# CONNECTEUR_4.net
KiCad netlist of a schematic drawn in Altium Designer
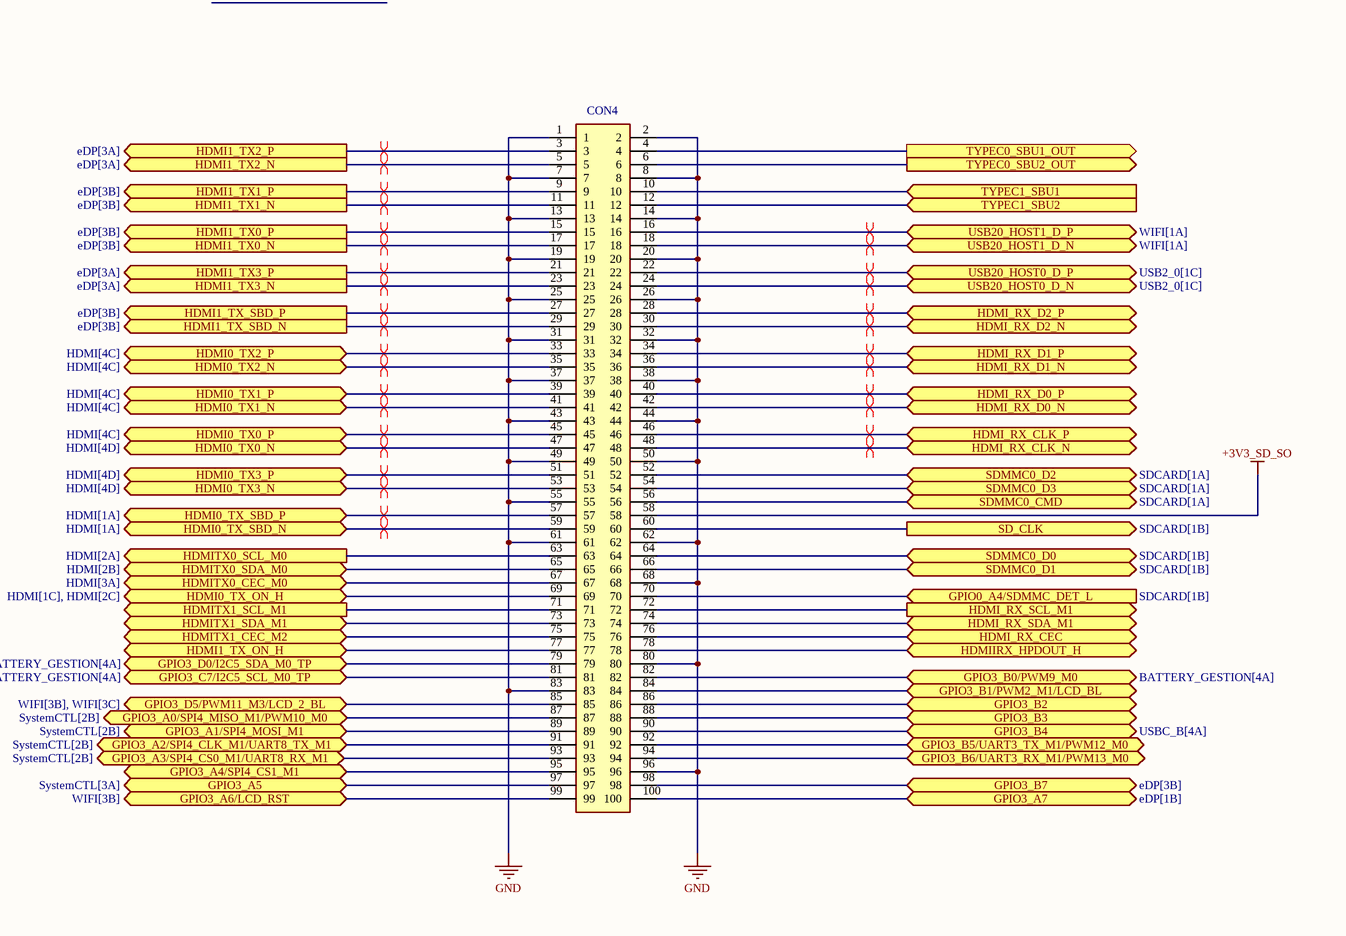
[diagram p0: CONNECTEUR_4.SchDoc, right]

(export (version "E")
  (design (tool "Eeschema 10.0.6"))
  (components
    (comp (ref "CON4")
      (value "DF40HC")
      (footprint "SamacSys:DF40HC30100DS04V51")
      (description "Stacking Board Connector, DF40 Series, Receptacle, 0.4 mm, 100, Surface Mount, G")
      (fields
        (field (name "MANUFACTURER_PART_NUMBER") "DF40HC(3.0)-100DS-0.4V(51")
        (field (name "MOUSER PART NUMBER") "798-DF40HC30100DS451")
      )
      (libsource (lib "SamacSys") (part "DF40HC(3.0)-100DS-0.4V(51)"))
    )
  )
  (nets
    (net (code "1") (name "+3V3_SD_SO") (class "Default")
      (node (ref "CON4") (pin "58") (pinfunction "58_58") (pintype "passive"))
    )
    (net (code "2") (name "/GPIO0_A4{slash}SDMMC_DET_L") (class "Default")
      (node (ref "CON4") (pin "70") (pinfunction "70_70") (pintype "passive"))
    )
    (net (code "3") (name "/GPIO3_A0{slash}SPI4_MISO_M1{slash}PWM10_M0") (class "Default")
      (node (ref "CON4") (pin "87") (pinfunction "87_87") (pintype "passive"))
    )
    (net (code "4") (name "/GPIO3_A1{slash}SPI4_MOSI_M1") (class "Default")
      (node (ref "CON4") (pin "89") (pinfunction "89_89") (pintype "passive"))
    )
    (net (code "5") (name "/GPIO3_A2{slash}SPI4_CLK_M1{slash}UART8_TX_M1") (class "Default")
      (node (ref "CON4") (pin "91") (pinfunction "91_91") (pintype "passive"))
    )
    (net (code "6") (name "/GPIO3_A3{slash}SPI4_CS0_M1{slash}UART8_RX_M1") (class "Default")
      (node (ref "CON4") (pin "93") (pinfunction "93_93") (pintype "passive"))
    )
    (net (code "7") (name "/GPIO3_A4{slash}SPI4_CS1_M1") (class "Default")
      (node (ref "CON4") (pin "95") (pinfunction "95_95") (pintype "passive"))
    )
    (net (code "8") (name "/GPIO3_A5") (class "Default")
      (node (ref "CON4") (pin "97") (pinfunction "97_97") (pintype "passive"))
    )
    (net (code "9") (name "/GPIO3_A6{slash}LCD_RST") (class "Default")
      (node (ref "CON4") (pin "99") (pinfunction "99_99") (pintype "passive"))
    )
    (net (code "10") (name "/GPIO3_A7") (class "Default")
      (node (ref "CON4") (pin "100") (pinfunction "100_100") (pintype "passive"))
    )
    (net (code "11") (name "/GPIO3_B0{slash}PWM9_M0") (class "Default")
      (node (ref "CON4") (pin "82") (pinfunction "82_82") (pintype "passive"))
    )
    (net (code "12") (name "/GPIO3_B1{slash}PWM2_M1{slash}LCD_BL") (class "Default")
      (node (ref "CON4") (pin "84") (pinfunction "84_84") (pintype "passive"))
    )
    (net (code "13") (name "/GPIO3_B2") (class "Default")
      (node (ref "CON4") (pin "86") (pinfunction "86_86") (pintype "passive"))
    )
    (net (code "14") (name "/GPIO3_B3") (class "Default")
      (node (ref "CON4") (pin "88") (pinfunction "88_88") (pintype "passive"))
    )
    (net (code "15") (name "/GPIO3_B4") (class "Default")
      (node (ref "CON4") (pin "90") (pinfunction "90_90") (pintype "passive"))
    )
    (net (code "16") (name "/GPIO3_B5{slash}UART3_TX_M1{slash}PWM12_M0") (class "Default")
      (node (ref "CON4") (pin "92") (pinfunction "92_92") (pintype "passive"))
    )
    (net (code "17") (name "/GPIO3_B6{slash}UART3_RX_M1{slash}PWM13_M0") (class "Default")
      (node (ref "CON4") (pin "94") (pinfunction "94_94") (pintype "passive"))
    )
    (net (code "18") (name "/GPIO3_B7") (class "Default")
      (node (ref "CON4") (pin "98") (pinfunction "98_98") (pintype "passive"))
    )
    (net (code "19") (name "/GPIO3_C7{slash}I2C5_SCL_M0_TP") (class "Default")
      (node (ref "CON4") (pin "81") (pinfunction "81_81") (pintype "passive"))
    )
    (net (code "20") (name "/GPIO3_D0{slash}I2C5_SDA_M0_TP") (class "Default")
      (node (ref "CON4") (pin "79") (pinfunction "79_79") (pintype "passive"))
    )
    (net (code "21") (name "/GPIO3_D5{slash}PWM11_M3{slash}LCD_2_BL") (class "Default")
      (node (ref "CON4") (pin "85") (pinfunction "85_85") (pintype "passive"))
    )
    (net (code "22") (name "/HDMI0_TX0_N") (class "Default")
      (node (ref "CON4") (pin "47") (pinfunction "47_47") (pintype "passive"))
    )
    (net (code "23") (name "/HDMI0_TX0_P") (class "Default")
      (node (ref "CON4") (pin "45") (pinfunction "45_45") (pintype "passive"))
    )
    (net (code "24") (name "/HDMI0_TX1_N") (class "Default")
      (node (ref "CON4") (pin "41") (pinfunction "41_41") (pintype "passive"))
    )
    (net (code "25") (name "/HDMI0_TX1_P") (class "Default")
      (node (ref "CON4") (pin "39") (pinfunction "39_39") (pintype "passive"))
    )
    (net (code "26") (name "/HDMI0_TX2_N") (class "Default")
      (node (ref "CON4") (pin "35") (pinfunction "35_35") (pintype "passive"))
    )
    (net (code "27") (name "/HDMI0_TX2_P") (class "Default")
      (node (ref "CON4") (pin "33") (pinfunction "33_33") (pintype "passive"))
    )
    (net (code "28") (name "/HDMI0_TX3_N") (class "Default")
      (node (ref "CON4") (pin "53") (pinfunction "53_53") (pintype "passive"))
    )
    (net (code "29") (name "/HDMI0_TX3_P") (class "Default")
      (node (ref "CON4") (pin "51") (pinfunction "51_51") (pintype "passive"))
    )
    (net (code "30") (name "/HDMI0_TX_ON_H") (class "Default")
      (node (ref "CON4") (pin "69") (pinfunction "69_69") (pintype "passive"))
    )
    (net (code "31") (name "/HDMI0_TX_SBD_N") (class "Default")
      (node (ref "CON4") (pin "59") (pinfunction "59_59") (pintype "passive"))
    )
    (net (code "32") (name "/HDMI0_TX_SBD_P") (class "Default")
      (node (ref "CON4") (pin "57") (pinfunction "57_57") (pintype "passive"))
    )
    (net (code "33") (name "/HDMI1_TX0_N") (class "Default")
      (node (ref "CON4") (pin "17") (pinfunction "17_17") (pintype "passive"))
    )
    (net (code "34") (name "/HDMI1_TX0_P") (class "Default")
      (node (ref "CON4") (pin "15") (pinfunction "15_15") (pintype "passive"))
    )
    (net (code "35") (name "/HDMI1_TX1_N") (class "Default")
      (node (ref "CON4") (pin "11") (pinfunction "11_11") (pintype "passive"))
    )
    (net (code "36") (name "/HDMI1_TX1_P") (class "Default")
      (node (ref "CON4") (pin "9") (pinfunction "9_9") (pintype "passive"))
    )
    (net (code "37") (name "/HDMI1_TX2_N") (class "Default")
      (node (ref "CON4") (pin "5") (pinfunction "5_5") (pintype "passive"))
    )
    (net (code "38") (name "/HDMI1_TX2_P") (class "Default")
      (node (ref "CON4") (pin "3") (pinfunction "3_3") (pintype "passive"))
    )
    (net (code "39") (name "/HDMI1_TX3_N") (class "Default")
      (node (ref "CON4") (pin "23") (pinfunction "23_23") (pintype "passive"))
    )
    (net (code "40") (name "/HDMI1_TX3_P") (class "Default")
      (node (ref "CON4") (pin "21") (pinfunction "21_21") (pintype "passive"))
    )
    (net (code "41") (name "/HDMI1_TX_ON_H") (class "Default")
      (node (ref "CON4") (pin "77") (pinfunction "77_77") (pintype "passive"))
    )
    (net (code "42") (name "/HDMI1_TX_SBD_N") (class "Default")
      (node (ref "CON4") (pin "29") (pinfunction "29_29") (pintype "passive"))
    )
    (net (code "43") (name "/HDMI1_TX_SBD_P") (class "Default")
      (node (ref "CON4") (pin "27") (pinfunction "27_27") (pintype "passive"))
    )
    (net (code "44") (name "/HDMIIRX_HPDOUT_H") (class "Default")
      (node (ref "CON4") (pin "78") (pinfunction "78_78") (pintype "passive"))
    )
    (net (code "45") (name "/HDMITX0_CEC_M0") (class "Default")
      (node (ref "CON4") (pin "67") (pinfunction "67_67") (pintype "passive"))
    )
    (net (code "46") (name "/HDMITX0_SCL_M0") (class "Default")
      (node (ref "CON4") (pin "63") (pinfunction "63_63") (pintype "passive"))
    )
    (net (code "47") (name "/HDMITX0_SDA_M0") (class "Default")
      (node (ref "CON4") (pin "65") (pinfunction "65_65") (pintype "passive"))
    )
    (net (code "48") (name "/HDMITX1_CEC_M2") (class "Default")
      (node (ref "CON4") (pin "75") (pinfunction "75_75") (pintype "passive"))
    )
    (net (code "49") (name "/HDMITX1_SCL_M1") (class "Default")
      (node (ref "CON4") (pin "71") (pinfunction "71_71") (pintype "passive"))
    )
    (net (code "50") (name "/HDMITX1_SDA_M1") (class "Default")
      (node (ref "CON4") (pin "73") (pinfunction "73_73") (pintype "passive"))
    )
    (net (code "51") (name "/HDMI_RX_CEC") (class "Default")
      (node (ref "CON4") (pin "76") (pinfunction "76_76") (pintype "passive"))
    )
    (net (code "52") (name "/HDMI_RX_CLK_N") (class "Default")
      (node (ref "CON4") (pin "48") (pinfunction "48_48") (pintype "passive"))
    )
    (net (code "53") (name "/HDMI_RX_CLK_P") (class "Default")
      (node (ref "CON4") (pin "46") (pinfunction "46_46") (pintype "passive"))
    )
    (net (code "54") (name "/HDMI_RX_D0_N") (class "Default")
      (node (ref "CON4") (pin "42") (pinfunction "42_42") (pintype "passive"))
    )
    (net (code "55") (name "/HDMI_RX_D0_P") (class "Default")
      (node (ref "CON4") (pin "40") (pinfunction "40_40") (pintype "passive"))
    )
    (net (code "56") (name "/HDMI_RX_D1_N") (class "Default")
      (node (ref "CON4") (pin "36") (pinfunction "36_36") (pintype "passive"))
    )
    (net (code "57") (name "/HDMI_RX_D1_P") (class "Default")
      (node (ref "CON4") (pin "34") (pinfunction "34_34") (pintype "passive"))
    )
    (net (code "58") (name "/HDMI_RX_D2_N") (class "Default")
      (node (ref "CON4") (pin "30") (pinfunction "30_30") (pintype "passive"))
    )
    (net (code "59") (name "/HDMI_RX_D2_P") (class "Default")
      (node (ref "CON4") (pin "28") (pinfunction "28_28") (pintype "passive"))
    )
    (net (code "60") (name "/HDMI_RX_SCL_M1") (class "Default")
      (node (ref "CON4") (pin "72") (pinfunction "72_72") (pintype "passive"))
    )
    (net (code "61") (name "/HDMI_RX_SDA_M1") (class "Default")
      (node (ref "CON4") (pin "74") (pinfunction "74_74") (pintype "passive"))
    )
    (net (code "62") (name "/SDMMC0_CMD") (class "Default")
      (node (ref "CON4") (pin "56") (pinfunction "56_56") (pintype "passive"))
    )
    (net (code "63") (name "/SDMMC0_D0") (class "Default")
      (node (ref "CON4") (pin "64") (pinfunction "64_64") (pintype "passive"))
    )
    (net (code "64") (name "/SDMMC0_D1") (class "Default")
      (node (ref "CON4") (pin "66") (pinfunction "66_66") (pintype "passive"))
    )
    (net (code "65") (name "/SDMMC0_D2") (class "Default")
      (node (ref "CON4") (pin "52") (pinfunction "52_52") (pintype "passive"))
    )
    (net (code "66") (name "/SDMMC0_D3") (class "Default")
      (node (ref "CON4") (pin "54") (pinfunction "54_54") (pintype "passive"))
    )
    (net (code "67") (name "/SD_CLK") (class "Default")
      (node (ref "CON4") (pin "60") (pinfunction "60_60") (pintype "passive"))
    )
    (net (code "68") (name "/TYPEC0_SBU1_OUT") (class "Default")
      (node (ref "CON4") (pin "4") (pinfunction "4_4") (pintype "passive"))
    )
    (net (code "69") (name "/TYPEC0_SBU2_OUT") (class "Default")
      (node (ref "CON4") (pin "6") (pinfunction "6_6") (pintype "passive"))
    )
    (net (code "70") (name "/TYPEC1_SBU1") (class "Default")
      (node (ref "CON4") (pin "10") (pinfunction "10_10") (pintype "passive"))
    )
    (net (code "71") (name "/TYPEC1_SBU2") (class "Default")
      (node (ref "CON4") (pin "12") (pinfunction "12_12") (pintype "passive"))
    )
    (net (code "72") (name "/USB20_HOST0_D_N") (class "Default")
      (node (ref "CON4") (pin "24") (pinfunction "24_24") (pintype "passive"))
    )
    (net (code "73") (name "/USB20_HOST0_D_P") (class "Default")
      (node (ref "CON4") (pin "22") (pinfunction "22_22") (pintype "passive"))
    )
    (net (code "74") (name "/USB20_HOST1_D_N") (class "Default")
      (node (ref "CON4") (pin "18") (pinfunction "18_18") (pintype "passive"))
    )
    (net (code "75") (name "/USB20_HOST1_D_P") (class "Default")
      (node (ref "CON4") (pin "16") (pinfunction "16_16") (pintype "passive"))
    )
    (net (code "76") (name "GND") (class "Default")
      (node (ref "CON4") (pin "1") (pinfunction "1_1") (pintype "passive"))
      (node (ref "CON4") (pin "13") (pinfunction "13_13") (pintype "passive"))
      (node (ref "CON4") (pin "14") (pinfunction "14_14") (pintype "passive"))
      (node (ref "CON4") (pin "19") (pinfunction "19_19") (pintype "passive"))
      (node (ref "CON4") (pin "2") (pinfunction "2_2") (pintype "passive"))
      (node (ref "CON4") (pin "20") (pinfunction "20_20") (pintype "passive"))
      (node (ref "CON4") (pin "25") (pinfunction "25_25") (pintype "passive"))
      (node (ref "CON4") (pin "26") (pinfunction "26_26") (pintype "passive"))
      (node (ref "CON4") (pin "31") (pinfunction "31_31") (pintype "passive"))
      (node (ref "CON4") (pin "32") (pinfunction "32_32") (pintype "passive"))
      (node (ref "CON4") (pin "37") (pinfunction "37_37") (pintype "passive"))
      (node (ref "CON4") (pin "38") (pinfunction "38_38") (pintype "passive"))
      (node (ref "CON4") (pin "43") (pinfunction "43_43") (pintype "passive"))
      (node (ref "CON4") (pin "44") (pinfunction "44_44") (pintype "passive"))
      (node (ref "CON4") (pin "49") (pinfunction "49_49") (pintype "passive"))
      (node (ref "CON4") (pin "50") (pinfunction "50_50") (pintype "passive"))
      (node (ref "CON4") (pin "55") (pinfunction "55_55") (pintype "passive"))
      (node (ref "CON4") (pin "61") (pinfunction "61_61") (pintype "passive"))
      (node (ref "CON4") (pin "62") (pinfunction "62_62") (pintype "passive"))
      (node (ref "CON4") (pin "68") (pinfunction "68_68") (pintype "passive"))
      (node (ref "CON4") (pin "7") (pinfunction "7_7") (pintype "passive"))
      (node (ref "CON4") (pin "8") (pinfunction "8_8") (pintype "passive"))
      (node (ref "CON4") (pin "80") (pinfunction "80_80") (pintype "passive"))
      (node (ref "CON4") (pin "83") (pinfunction "83_83") (pintype "passive"))
      (node (ref "CON4") (pin "96") (pinfunction "96_96") (pintype "passive"))
    )
  )
)
